# Gate_Driver.net
KiCad netlist of a schematic drawn in Altium Designer
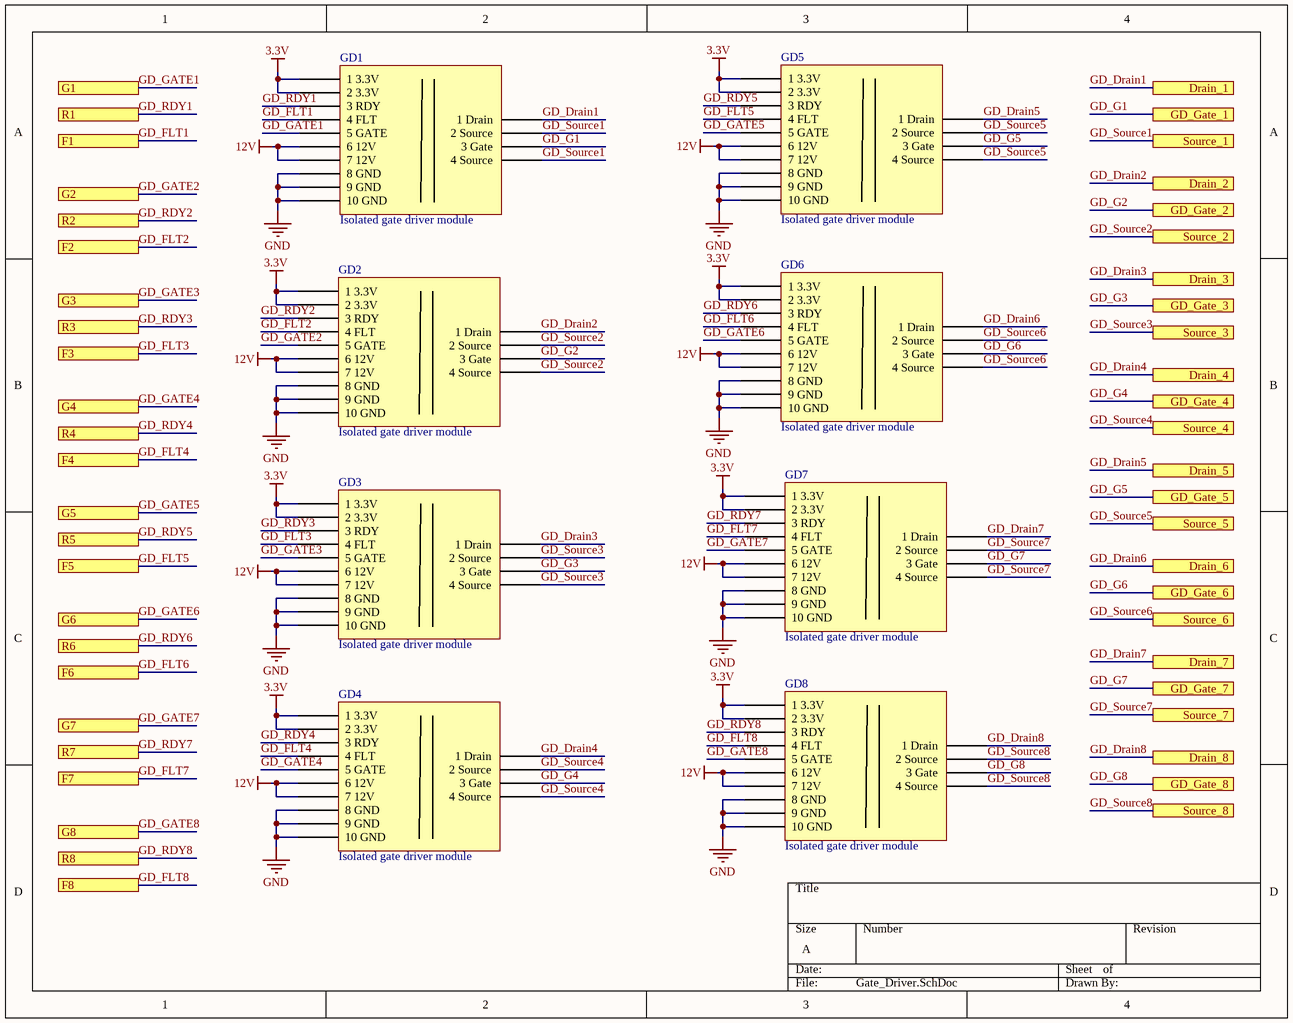
[diagram p0: Gate_Driver.SchDoc]

(export (version "E")
  (design (tool "Eeschema 10.0.6"))
  (components
    (comp (ref "GD1")
      (value "Isolated gate driver module")
      (footprint "Gate_Driver_horizontal")
      (description "10 + 4 Position Receptacle Connector 0.079\" (2.00mm) Through Hole Gold")
      (fields (field (name "MF") "Samtec Inc.") (field (name "CREATED") "2021_07_07_DArancibia"))
      (libsource (lib "H-Bridge 3-Leg - Lib") (part "Con_Isolated_gate_driver_module"))
    )
    (comp (ref "GD2")
      (value "Isolated gate driver module")
      (footprint "Gate_Driver_horizontal")
      (description "10 + 4 Position Receptacle Connector 0.079\" (2.00mm) Through Hole Gold")
      (fields (field (name "MF") "Samtec Inc.") (field (name "CREATED") "2021_07_07_DArancibia"))
      (libsource (lib "H-Bridge 3-Leg - Lib") (part "Con_Isolated_gate_driver_module"))
    )
    (comp (ref "GD3")
      (value "Isolated gate driver module")
      (footprint "Gate_Driver_horizontal")
      (description "10 + 4 Position Receptacle Connector 0.079\" (2.00mm) Through Hole Gold")
      (fields (field (name "MF") "Samtec Inc.") (field (name "CREATED") "2021_07_07_DArancibia"))
      (libsource (lib "H-Bridge 3-Leg - Lib") (part "Con_Isolated_gate_driver_module"))
    )
    (comp (ref "GD4")
      (value "Isolated gate driver module")
      (footprint "Gate_Driver_horizontal")
      (description "10 + 4 Position Receptacle Connector 0.079\" (2.00mm) Through Hole Gold")
      (fields (field (name "MF") "Samtec Inc.") (field (name "CREATED") "2021_07_07_DArancibia"))
      (libsource (lib "H-Bridge 3-Leg - Lib") (part "Con_Isolated_gate_driver_module"))
    )
    (comp (ref "GD5")
      (value "Isolated gate driver module")
      (footprint "Gate_Driver_horizontal")
      (description "10 + 4 Position Receptacle Connector 0.079\" (2.00mm) Through Hole Gold")
      (fields (field (name "MF") "Samtec Inc.") (field (name "CREATED") "2021_07_07_DArancibia"))
      (libsource (lib "H-Bridge 3-Leg - Lib") (part "Con_Isolated_gate_driver_module"))
    )
    (comp (ref "GD6")
      (value "Isolated gate driver module")
      (footprint "Gate_Driver_horizontal")
      (description "10 + 4 Position Receptacle Connector 0.079\" (2.00mm) Through Hole Gold")
      (fields (field (name "MF") "Samtec Inc.") (field (name "CREATED") "2021_07_07_DArancibia"))
      (libsource (lib "H-Bridge 3-Leg - Lib") (part "Con_Isolated_gate_driver_module"))
    )
    (comp (ref "GD7")
      (value "Isolated gate driver module")
      (footprint "Gate_Driver_horizontal")
      (description "10 + 4 Position Receptacle Connector 0.079\" (2.00mm) Through Hole Gold")
      (fields (field (name "MF") "Samtec Inc.") (field (name "CREATED") "2021_07_07_DArancibia"))
      (libsource (lib "H-Bridge 3-Leg - Lib") (part "Con_Isolated_gate_driver_module"))
    )
    (comp (ref "GD8")
      (value "Isolated gate driver module")
      (footprint "Gate_Driver_horizontal")
      (description "10 + 4 Position Receptacle Connector 0.079\" (2.00mm) Through Hole Gold")
      (fields (field (name "MF") "Samtec Inc.") (field (name "CREATED") "2021_07_07_DArancibia"))
      (libsource (lib "H-Bridge 3-Leg - Lib") (part "Con_Isolated_gate_driver_module"))
    )
  )
  (nets
    (net (code "1") (name "/GD_Drain1") (class "Default")
      (node (ref "GD1") (pin "11") (pinfunction "1_Drain_11") (pintype "passive"))
    )
    (net (code "2") (name "/GD_Drain2") (class "Default")
      (node (ref "GD2") (pin "11") (pinfunction "1_Drain_11") (pintype "passive"))
    )
    (net (code "3") (name "/GD_Drain3") (class "Default")
      (node (ref "GD3") (pin "11") (pinfunction "1_Drain_11") (pintype "passive"))
    )
    (net (code "4") (name "/GD_Drain4") (class "Default")
      (node (ref "GD4") (pin "11") (pinfunction "1_Drain_11") (pintype "passive"))
    )
    (net (code "5") (name "/GD_Drain5") (class "Default")
      (node (ref "GD5") (pin "11") (pinfunction "1_Drain_11") (pintype "passive"))
    )
    (net (code "6") (name "/GD_Drain6") (class "Default")
      (node (ref "GD6") (pin "11") (pinfunction "1_Drain_11") (pintype "passive"))
    )
    (net (code "7") (name "/GD_Drain7") (class "Default")
      (node (ref "GD7") (pin "11") (pinfunction "1_Drain_11") (pintype "passive"))
    )
    (net (code "8") (name "/GD_Drain8") (class "Default")
      (node (ref "GD8") (pin "11") (pinfunction "1_Drain_11") (pintype "passive"))
    )
    (net (code "9") (name "/GD_FLT1") (class "Default")
      (node (ref "GD1") (pin "4") (pinfunction "4_FLT_4") (pintype "passive"))
    )
    (net (code "10") (name "/GD_FLT2") (class "Default")
      (node (ref "GD2") (pin "4") (pinfunction "4_FLT_4") (pintype "passive"))
    )
    (net (code "11") (name "/GD_FLT3") (class "Default")
      (node (ref "GD3") (pin "4") (pinfunction "4_FLT_4") (pintype "passive"))
    )
    (net (code "12") (name "/GD_FLT4") (class "Default")
      (node (ref "GD4") (pin "4") (pinfunction "4_FLT_4") (pintype "passive"))
    )
    (net (code "13") (name "/GD_FLT5") (class "Default")
      (node (ref "GD5") (pin "4") (pinfunction "4_FLT_4") (pintype "passive"))
    )
    (net (code "14") (name "/GD_FLT6") (class "Default")
      (node (ref "GD6") (pin "4") (pinfunction "4_FLT_4") (pintype "passive"))
    )
    (net (code "15") (name "/GD_FLT7") (class "Default")
      (node (ref "GD7") (pin "4") (pinfunction "4_FLT_4") (pintype "passive"))
    )
    (net (code "16") (name "/GD_FLT8") (class "Default")
      (node (ref "GD8") (pin "4") (pinfunction "4_FLT_4") (pintype "passive"))
    )
    (net (code "17") (name "/GD_G1") (class "Default")
      (node (ref "GD1") (pin "13") (pinfunction "3_Gate_13") (pintype "passive"))
    )
    (net (code "18") (name "/GD_G2") (class "Default")
      (node (ref "GD2") (pin "13") (pinfunction "3_Gate_13") (pintype "passive"))
    )
    (net (code "19") (name "/GD_G3") (class "Default")
      (node (ref "GD3") (pin "13") (pinfunction "3_Gate_13") (pintype "passive"))
    )
    (net (code "20") (name "/GD_G4") (class "Default")
      (node (ref "GD4") (pin "13") (pinfunction "3_Gate_13") (pintype "passive"))
    )
    (net (code "21") (name "/GD_G5") (class "Default")
      (node (ref "GD5") (pin "13") (pinfunction "3_Gate_13") (pintype "passive"))
    )
    (net (code "22") (name "/GD_G6") (class "Default")
      (node (ref "GD6") (pin "13") (pinfunction "3_Gate_13") (pintype "passive"))
    )
    (net (code "23") (name "/GD_G7") (class "Default")
      (node (ref "GD7") (pin "13") (pinfunction "3_Gate_13") (pintype "passive"))
    )
    (net (code "24") (name "/GD_G8") (class "Default")
      (node (ref "GD8") (pin "13") (pinfunction "3_Gate_13") (pintype "passive"))
    )
    (net (code "25") (name "/GD_GATE1") (class "Default")
      (node (ref "GD1") (pin "5") (pinfunction "5_GATE_5") (pintype "passive"))
    )
    (net (code "26") (name "/GD_GATE2") (class "Default")
      (node (ref "GD2") (pin "5") (pinfunction "5_GATE_5") (pintype "passive"))
    )
    (net (code "27") (name "/GD_GATE3") (class "Default")
      (node (ref "GD3") (pin "5") (pinfunction "5_GATE_5") (pintype "passive"))
    )
    (net (code "28") (name "/GD_GATE4") (class "Default")
      (node (ref "GD4") (pin "5") (pinfunction "5_GATE_5") (pintype "passive"))
    )
    (net (code "29") (name "/GD_GATE5") (class "Default")
      (node (ref "GD5") (pin "5") (pinfunction "5_GATE_5") (pintype "passive"))
    )
    (net (code "30") (name "/GD_GATE6") (class "Default")
      (node (ref "GD6") (pin "5") (pinfunction "5_GATE_5") (pintype "passive"))
    )
    (net (code "31") (name "/GD_GATE7") (class "Default")
      (node (ref "GD7") (pin "5") (pinfunction "5_GATE_5") (pintype "passive"))
    )
    (net (code "32") (name "/GD_GATE8") (class "Default")
      (node (ref "GD8") (pin "5") (pinfunction "5_GATE_5") (pintype "passive"))
    )
    (net (code "33") (name "/GD_RDY1") (class "Default")
      (node (ref "GD1") (pin "3") (pinfunction "3_RDY_3") (pintype "passive"))
    )
    (net (code "34") (name "/GD_RDY2") (class "Default")
      (node (ref "GD2") (pin "3") (pinfunction "3_RDY_3") (pintype "passive"))
    )
    (net (code "35") (name "/GD_RDY3") (class "Default")
      (node (ref "GD3") (pin "3") (pinfunction "3_RDY_3") (pintype "passive"))
    )
    (net (code "36") (name "/GD_RDY4") (class "Default")
      (node (ref "GD4") (pin "3") (pinfunction "3_RDY_3") (pintype "passive"))
    )
    (net (code "37") (name "/GD_RDY5") (class "Default")
      (node (ref "GD5") (pin "3") (pinfunction "3_RDY_3") (pintype "passive"))
    )
    (net (code "38") (name "/GD_RDY6") (class "Default")
      (node (ref "GD6") (pin "3") (pinfunction "3_RDY_3") (pintype "passive"))
    )
    (net (code "39") (name "/GD_RDY7") (class "Default")
      (node (ref "GD7") (pin "3") (pinfunction "3_RDY_3") (pintype "passive"))
    )
    (net (code "40") (name "/GD_RDY8") (class "Default")
      (node (ref "GD8") (pin "3") (pinfunction "3_RDY_3") (pintype "passive"))
    )
    (net (code "41") (name "/GD_Source1") (class "Default")
      (node (ref "GD1") (pin "12") (pinfunction "2_Source_12") (pintype "passive"))
      (node (ref "GD1") (pin "14") (pinfunction "4_Source_14") (pintype "passive"))
    )
    (net (code "42") (name "/GD_Source2") (class "Default")
      (node (ref "GD2") (pin "12") (pinfunction "2_Source_12") (pintype "passive"))
      (node (ref "GD2") (pin "14") (pinfunction "4_Source_14") (pintype "passive"))
    )
    (net (code "43") (name "/GD_Source3") (class "Default")
      (node (ref "GD3") (pin "12") (pinfunction "2_Source_12") (pintype "passive"))
      (node (ref "GD3") (pin "14") (pinfunction "4_Source_14") (pintype "passive"))
    )
    (net (code "44") (name "/GD_Source4") (class "Default")
      (node (ref "GD4") (pin "12") (pinfunction "2_Source_12") (pintype "passive"))
      (node (ref "GD4") (pin "14") (pinfunction "4_Source_14") (pintype "passive"))
    )
    (net (code "45") (name "/GD_Source5") (class "Default")
      (node (ref "GD5") (pin "12") (pinfunction "2_Source_12") (pintype "passive"))
      (node (ref "GD5") (pin "14") (pinfunction "4_Source_14") (pintype "passive"))
    )
    (net (code "46") (name "/GD_Source6") (class "Default")
      (node (ref "GD6") (pin "12") (pinfunction "2_Source_12") (pintype "passive"))
      (node (ref "GD6") (pin "14") (pinfunction "4_Source_14") (pintype "passive"))
    )
    (net (code "47") (name "/GD_Source7") (class "Default")
      (node (ref "GD7") (pin "12") (pinfunction "2_Source_12") (pintype "passive"))
      (node (ref "GD7") (pin "14") (pinfunction "4_Source_14") (pintype "passive"))
    )
    (net (code "48") (name "/GD_Source8") (class "Default")
      (node (ref "GD8") (pin "12") (pinfunction "2_Source_12") (pintype "passive"))
      (node (ref "GD8") (pin "14") (pinfunction "4_Source_14") (pintype "passive"))
    )
    (net (code "49") (name "3.3V") (class "Default")
      (node (ref "GD1") (pin "1") (pinfunction "1_3.3V_1") (pintype "passive"))
      (node (ref "GD1") (pin "2") (pinfunction "2_3.3V_2") (pintype "passive"))
      (node (ref "GD2") (pin "1") (pinfunction "1_3.3V_1") (pintype "passive"))
      (node (ref "GD2") (pin "2") (pinfunction "2_3.3V_2") (pintype "passive"))
      (node (ref "GD3") (pin "1") (pinfunction "1_3.3V_1") (pintype "passive"))
      (node (ref "GD3") (pin "2") (pinfunction "2_3.3V_2") (pintype "passive"))
      (node (ref "GD4") (pin "1") (pinfunction "1_3.3V_1") (pintype "passive"))
      (node (ref "GD4") (pin "2") (pinfunction "2_3.3V_2") (pintype "passive"))
      (node (ref "GD5") (pin "1") (pinfunction "1_3.3V_1") (pintype "passive"))
      (node (ref "GD5") (pin "2") (pinfunction "2_3.3V_2") (pintype "passive"))
      (node (ref "GD6") (pin "1") (pinfunction "1_3.3V_1") (pintype "passive"))
      (node (ref "GD6") (pin "2") (pinfunction "2_3.3V_2") (pintype "passive"))
      (node (ref "GD7") (pin "1") (pinfunction "1_3.3V_1") (pintype "passive"))
      (node (ref "GD7") (pin "2") (pinfunction "2_3.3V_2") (pintype "passive"))
      (node (ref "GD8") (pin "1") (pinfunction "1_3.3V_1") (pintype "passive"))
      (node (ref "GD8") (pin "2") (pinfunction "2_3.3V_2") (pintype "passive"))
    )
    (net (code "50") (name "12V") (class "Default")
      (node (ref "GD1") (pin "6") (pinfunction "6_12V_6") (pintype "passive"))
      (node (ref "GD1") (pin "7") (pinfunction "7_12V_7") (pintype "passive"))
      (node (ref "GD2") (pin "6") (pinfunction "6_12V_6") (pintype "passive"))
      (node (ref "GD2") (pin "7") (pinfunction "7_12V_7") (pintype "passive"))
      (node (ref "GD3") (pin "6") (pinfunction "6_12V_6") (pintype "passive"))
      (node (ref "GD3") (pin "7") (pinfunction "7_12V_7") (pintype "passive"))
      (node (ref "GD4") (pin "6") (pinfunction "6_12V_6") (pintype "passive"))
      (node (ref "GD4") (pin "7") (pinfunction "7_12V_7") (pintype "passive"))
      (node (ref "GD5") (pin "6") (pinfunction "6_12V_6") (pintype "passive"))
      (node (ref "GD5") (pin "7") (pinfunction "7_12V_7") (pintype "passive"))
      (node (ref "GD6") (pin "6") (pinfunction "6_12V_6") (pintype "passive"))
      (node (ref "GD6") (pin "7") (pinfunction "7_12V_7") (pintype "passive"))
      (node (ref "GD7") (pin "6") (pinfunction "6_12V_6") (pintype "passive"))
      (node (ref "GD7") (pin "7") (pinfunction "7_12V_7") (pintype "passive"))
      (node (ref "GD8") (pin "6") (pinfunction "6_12V_6") (pintype "passive"))
      (node (ref "GD8") (pin "7") (pinfunction "7_12V_7") (pintype "passive"))
    )
    (net (code "51") (name "GND") (class "Default")
      (node (ref "GD1") (pin "10") (pinfunction "10_GND_10") (pintype "passive"))
      (node (ref "GD1") (pin "8") (pinfunction "8_GND_8") (pintype "passive"))
      (node (ref "GD1") (pin "9") (pinfunction "9_GND_9") (pintype "passive"))
      (node (ref "GD2") (pin "10") (pinfunction "10_GND_10") (pintype "passive"))
      (node (ref "GD2") (pin "8") (pinfunction "8_GND_8") (pintype "passive"))
      (node (ref "GD2") (pin "9") (pinfunction "9_GND_9") (pintype "passive"))
      (node (ref "GD3") (pin "10") (pinfunction "10_GND_10") (pintype "passive"))
      (node (ref "GD3") (pin "8") (pinfunction "8_GND_8") (pintype "passive"))
      (node (ref "GD3") (pin "9") (pinfunction "9_GND_9") (pintype "passive"))
      (node (ref "GD4") (pin "10") (pinfunction "10_GND_10") (pintype "passive"))
      (node (ref "GD4") (pin "8") (pinfunction "8_GND_8") (pintype "passive"))
      (node (ref "GD4") (pin "9") (pinfunction "9_GND_9") (pintype "passive"))
      (node (ref "GD5") (pin "10") (pinfunction "10_GND_10") (pintype "passive"))
      (node (ref "GD5") (pin "8") (pinfunction "8_GND_8") (pintype "passive"))
      (node (ref "GD5") (pin "9") (pinfunction "9_GND_9") (pintype "passive"))
      (node (ref "GD6") (pin "10") (pinfunction "10_GND_10") (pintype "passive"))
      (node (ref "GD6") (pin "8") (pinfunction "8_GND_8") (pintype "passive"))
      (node (ref "GD6") (pin "9") (pinfunction "9_GND_9") (pintype "passive"))
      (node (ref "GD7") (pin "10") (pinfunction "10_GND_10") (pintype "passive"))
      (node (ref "GD7") (pin "8") (pinfunction "8_GND_8") (pintype "passive"))
      (node (ref "GD7") (pin "9") (pinfunction "9_GND_9") (pintype "passive"))
      (node (ref "GD8") (pin "10") (pinfunction "10_GND_10") (pintype "passive"))
      (node (ref "GD8") (pin "8") (pinfunction "8_GND_8") (pintype "passive"))
      (node (ref "GD8") (pin "9") (pinfunction "9_GND_9") (pintype "passive"))
    )
  )
)
